# uszko.net
KiCad netlist of a schematic drawn in EAGLE
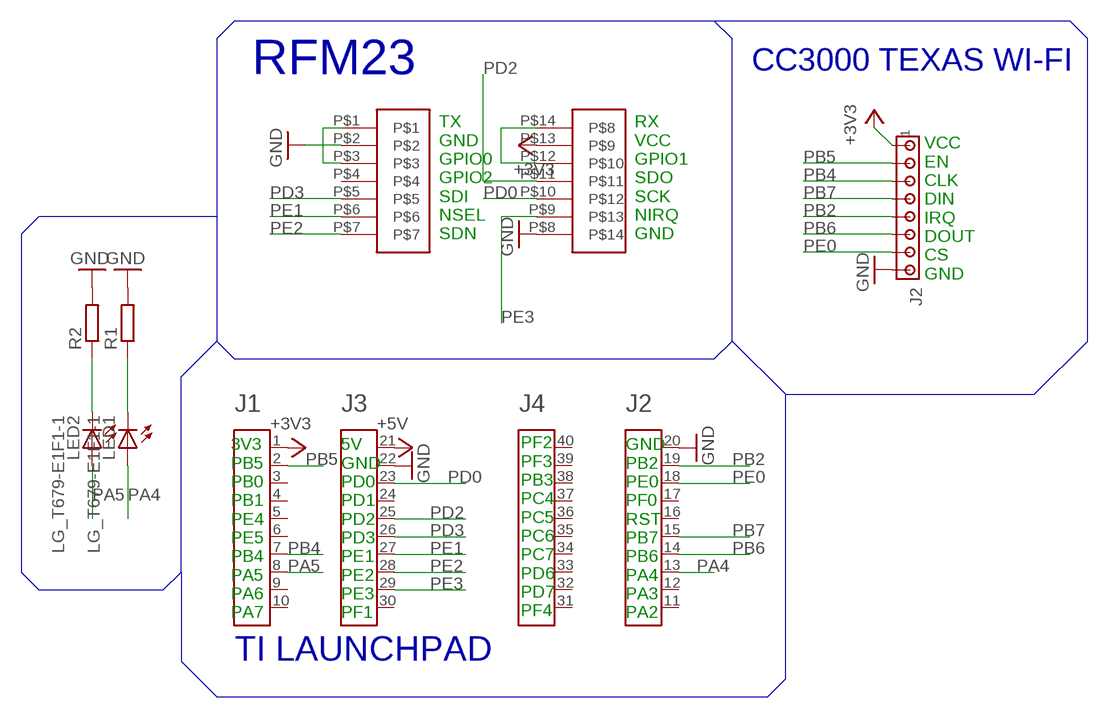
[diagram p0: schematic, sheet 1]

(export (version "E")
  (design (tool "Eeschema 10.0.6"))
  (components
    (comp (ref "A1")
      (value "HEADER4X10-BOOSTERPACK")
      (footprint "eagle-import:4X10-BOOSTERPACK")
      (libsource (lib "eagle-import") (part "HEADER4X10-BOOSTERPACK"))
    )
    (comp (ref "J2")
      (value "MTA08-100")
      (footprint "eagle-import:10X08MTA")
      (libsource (lib "eagle-import") (part "MTA08-100"))
    )
    (comp (ref "LED1")
      (value "LG_T679-E1F1-1")
      (footprint "eagle-import:PLCC2")
      (libsource (lib "eagle-import") (part "_T679-?-1E1F1LG"))
    )
    (comp (ref "LED2")
      (value "LG_T679-E1F1-1")
      (footprint "eagle-import:PLCC2")
      (libsource (lib "eagle-import") (part "_T679-?-1E1F1LG"))
    )
    (comp (ref "R1")
      (value "R-EU_R0805")
      (footprint "eagle-import:R0805")
      (libsource (lib "eagle-import") (part "R-EU_R0805"))
    )
    (comp (ref "R2")
      (value "R-EU_R0805")
      (footprint "eagle-import:R0805")
      (libsource (lib "eagle-import") (part "R-EU_R0805"))
    )
    (comp (ref "U$1")
      (value "2X7PIN")
      (footprint "eagle-import:2X7PINCON")
      (libsource (lib "eagle-import") (part "2X7PIN"))
    )
  )
  (nets
    (net (code "1") (name "+3V3") (class "Default")
      (node (ref "A1") (pin "1") (pinfunction "P$1_1") (pintype "bidirectional"))
      (node (ref "J2") (pin "1") (pinfunction "1_1") (pintype "passive"))
      (node (ref "U$1") (pin "P$13") (pinfunction "P$9_P$13") (pintype "bidirectional"))
    )
    (net (code "2") (name "+5V") (class "Default")
      (node (ref "A1") (pin "21") (pinfunction "P$21_21") (pintype "bidirectional"))
    )
    (net (code "3") (name "/PA4") (class "Default")
      (node (ref "A1") (pin "13") (pinfunction "P$13_13") (pintype "bidirectional"))
      (node (ref "LED1") (pin "A") (pinfunction "A_A") (pintype "passive"))
    )
    (net (code "4") (name "/PA5") (class "Default")
      (node (ref "A1") (pin "8") (pinfunction "P$8_8") (pintype "bidirectional"))
      (node (ref "LED2") (pin "A") (pinfunction "A_A") (pintype "passive"))
    )
    (net (code "5") (name "/PB2") (class "Default")
      (node (ref "A1") (pin "19") (pinfunction "P$19_19") (pintype "bidirectional"))
      (node (ref "J2") (pin "5") (pinfunction "5_5") (pintype "passive"))
    )
    (net (code "6") (name "/PB4") (class "Default")
      (node (ref "A1") (pin "7") (pinfunction "P$7_7") (pintype "bidirectional"))
      (node (ref "J2") (pin "3") (pinfunction "3_3") (pintype "passive"))
    )
    (net (code "7") (name "/PB5") (class "Default")
      (node (ref "A1") (pin "2") (pinfunction "P$2_2") (pintype "bidirectional"))
      (node (ref "J2") (pin "2") (pinfunction "2_2") (pintype "passive"))
    )
    (net (code "8") (name "/PB6") (class "Default")
      (node (ref "A1") (pin "14") (pinfunction "P$14_14") (pintype "bidirectional"))
      (node (ref "J2") (pin "6") (pinfunction "6_6") (pintype "passive"))
    )
    (net (code "9") (name "/PB7") (class "Default")
      (node (ref "A1") (pin "15") (pinfunction "P$15_15") (pintype "bidirectional"))
      (node (ref "J2") (pin "4") (pinfunction "4_4") (pintype "passive"))
    )
    (net (code "10") (name "/PD0") (class "Default")
      (node (ref "A1") (pin "23") (pinfunction "P$23_23") (pintype "bidirectional"))
      (node (ref "U$1") (pin "P$10") (pinfunction "P$12_P$10") (pintype "bidirectional"))
    )
    (net (code "11") (name "/PD2") (class "Default")
      (node (ref "A1") (pin "25") (pinfunction "P$25_25") (pintype "bidirectional"))
      (node (ref "U$1") (pin "P$11") (pinfunction "P$11_P$11") (pintype "bidirectional"))
    )
    (net (code "12") (name "/PD3") (class "Default")
      (node (ref "A1") (pin "26") (pinfunction "P$26_26") (pintype "bidirectional"))
      (node (ref "U$1") (pin "P$5") (pinfunction "P$5_P$5") (pintype "bidirectional"))
    )
    (net (code "13") (name "/PE0") (class "Default")
      (node (ref "A1") (pin "18") (pinfunction "P$18_18") (pintype "bidirectional"))
      (node (ref "J2") (pin "7") (pinfunction "7_7") (pintype "passive"))
    )
    (net (code "14") (name "/PE1") (class "Default")
      (node (ref "A1") (pin "27") (pinfunction "P$27_27") (pintype "bidirectional"))
      (node (ref "U$1") (pin "P$6") (pinfunction "P$6_P$6") (pintype "bidirectional"))
    )
    (net (code "15") (name "/PE2") (class "Default")
      (node (ref "A1") (pin "28") (pinfunction "P$28_28") (pintype "bidirectional"))
      (node (ref "U$1") (pin "P$7") (pinfunction "P$7_P$7") (pintype "bidirectional"))
    )
    (net (code "16") (name "/PE3") (class "Default")
      (node (ref "A1") (pin "29") (pinfunction "P$29_29") (pintype "bidirectional"))
      (node (ref "U$1") (pin "P$9") (pinfunction "P$13_P$9") (pintype "bidirectional"))
    )
    (net (code "17") (name "GND") (class "Default")
      (node (ref "A1") (pin "20") (pinfunction "P$20_20") (pintype "bidirectional"))
      (node (ref "A1") (pin "22") (pinfunction "P$22_22") (pintype "bidirectional"))
      (node (ref "J2") (pin "8") (pinfunction "8_8") (pintype "passive"))
      (node (ref "R1") (pin "2") (pinfunction "2_2") (pintype "passive"))
      (node (ref "R2") (pin "2") (pinfunction "2_2") (pintype "passive"))
      (node (ref "U$1") (pin "P$2") (pinfunction "P$2_P$2") (pintype "bidirectional"))
      (node (ref "U$1") (pin "P$8") (pinfunction "P$14_P$8") (pintype "bidirectional"))
    )
    (net (code "18") (name "Net-(LED1-PadC)") (class "Default")
      (node (ref "LED1") (pin "C") (pinfunction "C_C") (pintype "passive"))
      (node (ref "R1") (pin "1") (pinfunction "1_1") (pintype "passive"))
    )
    (net (code "19") (name "Net-(LED2-PadC)") (class "Default")
      (node (ref "LED2") (pin "C") (pinfunction "C_C") (pintype "passive"))
      (node (ref "R2") (pin "1") (pinfunction "1_1") (pintype "passive"))
    )
    (net (code "20") (name "Net-(U$1-P$10)") (class "Default")
      (node (ref "U$1") (pin "P$12") (pinfunction "P$10_P$12") (pintype "bidirectional"))
      (node (ref "U$1") (pin "P$14") (pinfunction "P$8_P$14") (pintype "bidirectional"))
    )
    (net (code "21") (name "Net-(U$1-PadP$1)") (class "Default")
      (node (ref "U$1") (pin "P$1") (pinfunction "P$1_P$1") (pintype "bidirectional"))
      (node (ref "U$1") (pin "P$3") (pinfunction "P$3_P$3") (pintype "bidirectional"))
    )
    (net (code "22") (name "unconnected-(A1-P$3-Pad3)") (class "Default")
      (node (ref "A1") (pin "3") (pinfunction "P$3_3") (pintype "bidirectional"))
    )
    (net (code "23") (name "unconnected-(A1-P$4-Pad4)") (class "Default")
      (node (ref "A1") (pin "4") (pinfunction "P$4_4") (pintype "bidirectional"))
    )
    (net (code "24") (name "unconnected-(A1-P$5-Pad5)") (class "Default")
      (node (ref "A1") (pin "5") (pinfunction "P$5_5") (pintype "bidirectional"))
    )
    (net (code "25") (name "unconnected-(A1-P$6-Pad6)") (class "Default")
      (node (ref "A1") (pin "6") (pinfunction "P$6_6") (pintype "bidirectional"))
    )
    (net (code "26") (name "unconnected-(A1-P$9-Pad9)") (class "Default")
      (node (ref "A1") (pin "9") (pinfunction "P$9_9") (pintype "bidirectional"))
    )
    (net (code "27") (name "unconnected-(A1-P$10-Pad10)") (class "Default")
      (node (ref "A1") (pin "10") (pinfunction "P$10_10") (pintype "bidirectional"))
    )
    (net (code "28") (name "unconnected-(A1-P$11-Pad11)") (class "Default")
      (node (ref "A1") (pin "11") (pinfunction "P$11_11") (pintype "bidirectional"))
    )
    (net (code "29") (name "unconnected-(A1-P$12-Pad12)") (class "Default")
      (node (ref "A1") (pin "12") (pinfunction "P$12_12") (pintype "bidirectional"))
    )
    (net (code "30") (name "unconnected-(A1-P$16-Pad16)") (class "Default")
      (node (ref "A1") (pin "16") (pinfunction "P$16_16") (pintype "bidirectional"))
    )
    (net (code "31") (name "unconnected-(A1-P$17-Pad17)") (class "Default")
      (node (ref "A1") (pin "17") (pinfunction "P$17_17") (pintype "bidirectional"))
    )
    (net (code "32") (name "unconnected-(A1-P$24-Pad24)") (class "Default")
      (node (ref "A1") (pin "24") (pinfunction "P$24_24") (pintype "bidirectional"))
    )
    (net (code "33") (name "unconnected-(A1-P$30-Pad30)") (class "Default")
      (node (ref "A1") (pin "30") (pinfunction "P$30_30") (pintype "bidirectional"))
    )
    (net (code "34") (name "unconnected-(A1-P$31-Pad31)") (class "Default")
      (node (ref "A1") (pin "31") (pinfunction "P$31_31") (pintype "bidirectional"))
    )
    (net (code "35") (name "unconnected-(A1-P$32-Pad32)") (class "Default")
      (node (ref "A1") (pin "32") (pinfunction "P$32_32") (pintype "bidirectional"))
    )
    (net (code "36") (name "unconnected-(A1-P$33-Pad33)") (class "Default")
      (node (ref "A1") (pin "33") (pinfunction "P$33_33") (pintype "bidirectional"))
    )
    (net (code "37") (name "unconnected-(A1-P$34-Pad34)") (class "Default")
      (node (ref "A1") (pin "34") (pinfunction "P$34_34") (pintype "bidirectional"))
    )
    (net (code "38") (name "unconnected-(A1-P$35-Pad35)") (class "Default")
      (node (ref "A1") (pin "35") (pinfunction "P$35_35") (pintype "bidirectional"))
    )
    (net (code "39") (name "unconnected-(A1-P$36-Pad36)") (class "Default")
      (node (ref "A1") (pin "36") (pinfunction "P$36_36") (pintype "bidirectional"))
    )
    (net (code "40") (name "unconnected-(A1-P$37-Pad37)") (class "Default")
      (node (ref "A1") (pin "37") (pinfunction "P$37_37") (pintype "bidirectional"))
    )
    (net (code "41") (name "unconnected-(A1-P$38-Pad38)") (class "Default")
      (node (ref "A1") (pin "38") (pinfunction "P$38_38") (pintype "bidirectional"))
    )
    (net (code "42") (name "unconnected-(A1-P$39-Pad39)") (class "Default")
      (node (ref "A1") (pin "39") (pinfunction "P$39_39") (pintype "bidirectional"))
    )
    (net (code "43") (name "unconnected-(A1-P$40-Pad40)") (class "Default")
      (node (ref "A1") (pin "40") (pinfunction "P$40_40") (pintype "bidirectional"))
    )
    (net (code "44") (name "unconnected-(U$1-PadP$4)") (class "Default")
      (node (ref "U$1") (pin "P$4") (pinfunction "P$4_P$4") (pintype "bidirectional"))
    )
  )
)
